# BME688.net
KiCad netlist of a schematic drawn in Altium Designer
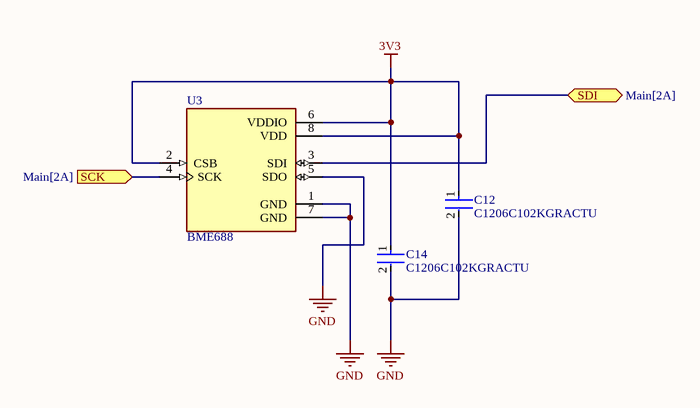
[diagram p0: BME688.SchDoc]

(export (version "E")
  (design (tool "Eeschema 10.0.6"))
  (components
    (comp (ref "C12")
      (value "C1206C102KGRACTU")
      (footprint "FP-C1206C-EF-IPC_A")
      (description "CAP CER 1000PF 2KV X7R 1206")
      (fields (field (name "VOLTAGE") "2kV") (field (name "TOLERANCE") "10%"))
      (libsource (lib "Altium Content Vault") (part "b4654b650e69147ec39a6b967a45e02"))
    )
    (comp (ref "C14")
      (value "C1206C102KGRACTU")
      (footprint "FP-C1206C-EF-IPC_A")
      (description "CAP CER 1000PF 2KV X7R 1206")
      (fields (field (name "VOLTAGE") "2kV") (field (name "TOLERANCE") "10%"))
      (libsource (lib "Altium Content Vault") (part "b4654b650e69147ec39a6b967a45e02"))
    )
    (comp (ref "U3")
      (value "BME688")
      (footprint "BME680")
      (description "Gas sensor measuring relative humidity, barometric pressure, ambient temperature and gas (VOC)")
      (libsource (lib "BME688") (part "BME688"))
    )
  )
  (nets
    (net (code "1") (name "/SCK") (class "Default")
      (node (ref "U3") (pin "4") (pinfunction "SCK_4") (pintype "input"))
    )
    (net (code "2") (name "/SDI") (class "Default")
      (node (ref "U3") (pin "3") (pinfunction "SDI_3") (pintype "bidirectional"))
    )
    (net (code "3") (name "3V3") (class "Default")
      (node (ref "C12") (pin "1") (pinfunction "1_1") (pintype "passive"))
      (node (ref "C14") (pin "1") (pinfunction "1_1") (pintype "passive"))
      (node (ref "U3") (pin "2") (pinfunction "CSB_2") (pintype "input"))
      (node (ref "U3") (pin "6") (pinfunction "VDDIO_6") (pintype "power_in"))
      (node (ref "U3") (pin "8") (pinfunction "VDD_8") (pintype "power_in"))
    )
    (net (code "4") (name "GND") (class "Default")
      (node (ref "C12") (pin "2") (pinfunction "2_2") (pintype "passive"))
      (node (ref "C14") (pin "2") (pinfunction "2_2") (pintype "passive"))
      (node (ref "U3") (pin "1") (pinfunction "GND_1") (pintype "power_in"))
      (node (ref "U3") (pin "5") (pinfunction "SDO_5") (pintype "bidirectional"))
      (node (ref "U3") (pin "7") (pinfunction "GND_7") (pintype "power_in"))
    )
  )
)
